# ATEM_Transmitter_v2.net
KiCad netlist of a schematic drawn in EAGLE
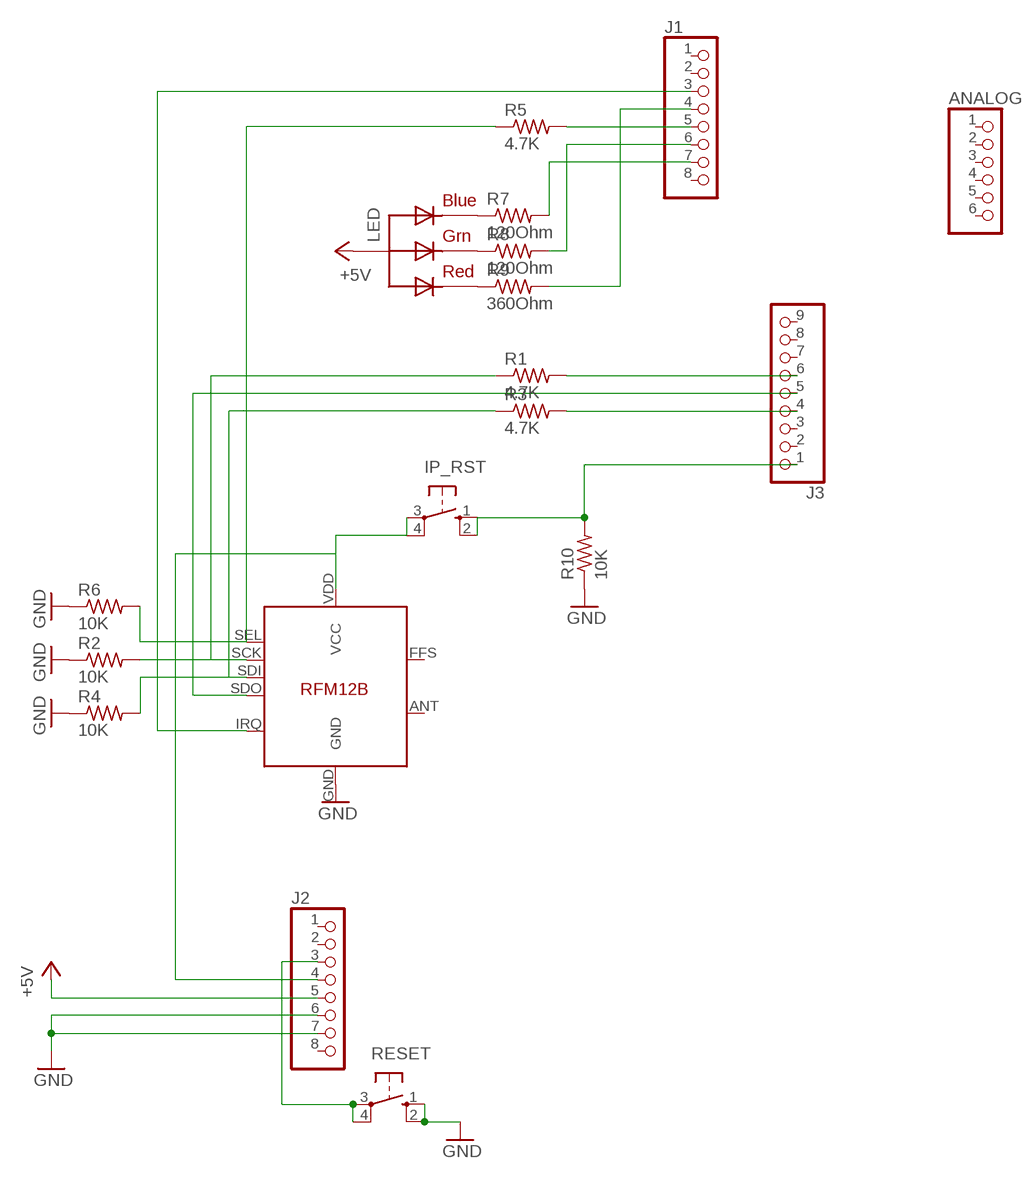
[diagram p0: schematic, sheet 1]

(export (version "E")
  (design (tool "Eeschema 10.0.6"))
  (components
    (comp (ref "ANALOG")
      (value "PINHD-1X6")
      (footprint "eagle-import:1X06")
      (libsource (lib "eagle-import") (part "PINHD-1X6"))
    )
    (comp (ref "IP_RST")
      (value "10-XX")
      (footprint "eagle-import:B3F-10XX")
      (libsource (lib "eagle-import") (part "10-XX"))
    )
    (comp (ref "J1")
      (value "PINHD-1X8TH")
      (footprint "eagle-import:1X08-TH")
      (libsource (lib "eagle-import") (part "PINHD-1X8TH"))
    )
    (comp (ref "J2")
      (value "PINHD-1X8TH")
      (footprint "eagle-import:1X08-TH")
      (libsource (lib "eagle-import") (part "PINHD-1X8TH"))
    )
    (comp (ref "J3")
      (value "PINHD-1X9")
      (footprint "eagle-import:1X09")
      (libsource (lib "eagle-import") (part "PINHD-1X9"))
    )
    (comp (ref "LED")
      (value "RGBLED_CA-5MM")
      (footprint "eagle-import:LED5MMRGB")
      (libsource (lib "eagle-import") (part "RGBLED_CA-5MM"))
    )
    (comp (ref "R1")
      (value "4.7K")
      (footprint "eagle-import:R0805")
      (libsource (lib "eagle-import") (part "R-US_R0805"))
    )
    (comp (ref "R2")
      (value "10K")
      (footprint "eagle-import:R0805")
      (libsource (lib "eagle-import") (part "R-US_R0805"))
    )
    (comp (ref "R3")
      (value "4.7K")
      (footprint "eagle-import:R0805")
      (libsource (lib "eagle-import") (part "R-US_R0805"))
    )
    (comp (ref "R4")
      (value "10K")
      (footprint "eagle-import:R0805")
      (libsource (lib "eagle-import") (part "R-US_R0805"))
    )
    (comp (ref "R5")
      (value "4.7K")
      (footprint "eagle-import:R0805")
      (libsource (lib "eagle-import") (part "R-US_R0805"))
    )
    (comp (ref "R6")
      (value "10K")
      (footprint "eagle-import:R0805")
      (libsource (lib "eagle-import") (part "R-US_R0805"))
    )
    (comp (ref "R7")
      (value "120Ohm")
      (footprint "eagle-import:R0805")
      (libsource (lib "eagle-import") (part "R-US_R0805"))
    )
    (comp (ref "R8")
      (value "120Ohm")
      (footprint "eagle-import:R0805")
      (libsource (lib "eagle-import") (part "R-US_R0805"))
    )
    (comp (ref "R9")
      (value "360Ohm")
      (footprint "eagle-import:R0805")
      (libsource (lib "eagle-import") (part "R-US_R0805"))
    )
    (comp (ref "R10")
      (value "10K")
      (footprint "eagle-import:R0805")
      (libsource (lib "eagle-import") (part "R-US_R0805"))
    )
    (comp (ref "RESET")
      (value "10-XX")
      (footprint "eagle-import:B3F-10XX")
      (libsource (lib "eagle-import") (part "10-XX"))
    )
    (comp (ref "U$2")
      (value "RFM12B")
      (footprint "eagle-import:LH-LIBRARY_RFM12B")
      (libsource (lib "eagle-import") (part "LH-LIBRARY_RFM12B"))
    )
  )
  (nets
    (net (code "1") (name "+5V") (class "Default")
      (node (ref "J2") (pin "5") (pinfunction "5_5") (pintype "passive"))
      (node (ref "LED") (pin "2") (pinfunction "VCC_2") (pintype "bidirectional"))
    )
    (net (code "2") (name "GND") (class "Default")
      (node (ref "J2") (pin "7") (pinfunction "7_7") (pintype "passive"))
      (node (ref "R10") (pin "1") (pinfunction "1_1") (pintype "passive"))
      (node (ref "R2") (pin "1") (pinfunction "1_1") (pintype "passive"))
      (node (ref "R4") (pin "1") (pinfunction "1_1") (pintype "passive"))
      (node (ref "R6") (pin "1") (pinfunction "1_1") (pintype "passive"))
      (node (ref "RESET") (pin "1") (pinfunction "S_1") (pintype "passive"))
      (node (ref "RESET") (pin "2") (pinfunction "S1_2") (pintype "passive"))
      (node (ref "U$2") (pin "GND") (pinfunction "GND_GND") (pintype "power_in"))
    )
    (net (code "3") (name "Net-(IP_RST-P)") (class "Default")
      (node (ref "IP_RST") (pin "3") (pinfunction "P_3") (pintype "passive"))
      (node (ref "IP_RST") (pin "4") (pinfunction "P1_4") (pintype "passive"))
      (node (ref "J2") (pin "4") (pinfunction "4_4") (pintype "passive"))
      (node (ref "U$2") (pin "VDD") (pinfunction "VCC_VDD") (pintype "power_in"))
    )
    (net (code "4") (name "Net-(IP_RST-S)") (class "Default")
      (node (ref "IP_RST") (pin "1") (pinfunction "S_1") (pintype "passive"))
      (node (ref "IP_RST") (pin "2") (pinfunction "S1_2") (pintype "passive"))
      (node (ref "J3") (pin "1") (pinfunction "1_1") (pintype "passive"))
      (node (ref "R10") (pin "2") (pinfunction "2_2") (pintype "passive"))
    )
    (net (code "5") (name "Net-(J1-Pad3)") (class "Default")
      (node (ref "J1") (pin "3") (pinfunction "3_3") (pintype "passive"))
      (node (ref "U$2") (pin "IRQ") (pinfunction "IRQ_IRQ") (pintype "open_collector"))
    )
    (net (code "6") (name "Net-(J1-Pad4)") (class "Default")
      (node (ref "J1") (pin "4") (pinfunction "4_4") (pintype "passive"))
      (node (ref "R9") (pin "2") (pinfunction "2_2") (pintype "passive"))
    )
    (net (code "7") (name "Net-(J1-Pad5)") (class "Default")
      (node (ref "J1") (pin "5") (pinfunction "5_5") (pintype "passive"))
      (node (ref "R5") (pin "2") (pinfunction "2_2") (pintype "passive"))
    )
    (net (code "8") (name "Net-(J1-Pad6)") (class "Default")
      (node (ref "J1") (pin "6") (pinfunction "6_6") (pintype "passive"))
      (node (ref "R8") (pin "2") (pinfunction "2_2") (pintype "passive"))
    )
    (net (code "9") (name "Net-(J1-Pad7)") (class "Default")
      (node (ref "J1") (pin "7") (pinfunction "7_7") (pintype "passive"))
      (node (ref "R7") (pin "2") (pinfunction "2_2") (pintype "passive"))
    )
    (net (code "10") (name "Net-(J3-Pad4)") (class "Default")
      (node (ref "J3") (pin "4") (pinfunction "4_4") (pintype "passive"))
      (node (ref "R3") (pin "2") (pinfunction "2_2") (pintype "passive"))
    )
    (net (code "11") (name "Net-(J3-Pad5)") (class "Default")
      (node (ref "J3") (pin "5") (pinfunction "5_5") (pintype "passive"))
      (node (ref "U$2") (pin "SDO") (pinfunction "SDO_SDO") (pintype "output"))
    )
    (net (code "12") (name "Net-(J3-Pad6)") (class "Default")
      (node (ref "J3") (pin "6") (pinfunction "6_6") (pintype "passive"))
      (node (ref "R1") (pin "2") (pinfunction "2_2") (pintype "passive"))
    )
    (net (code "13") (name "Net-(LED-BLUE)") (class "Default")
      (node (ref "LED") (pin "4") (pinfunction "BLUE_4") (pintype "bidirectional"))
      (node (ref "R7") (pin "1") (pinfunction "1_1") (pintype "passive"))
    )
    (net (code "14") (name "Net-(LED-GREEN)") (class "Default")
      (node (ref "LED") (pin "3") (pinfunction "GREEN_3") (pintype "bidirectional"))
      (node (ref "R8") (pin "1") (pinfunction "1_1") (pintype "passive"))
    )
    (net (code "15") (name "Net-(LED-RED)") (class "Default")
      (node (ref "LED") (pin "1") (pinfunction "RED_1") (pintype "bidirectional"))
      (node (ref "R9") (pin "1") (pinfunction "1_1") (pintype "passive"))
    )
    (net (code "16") (name "Net-(R1-Pad1)") (class "Default")
      (node (ref "R1") (pin "1") (pinfunction "1_1") (pintype "passive"))
      (node (ref "R2") (pin "2") (pinfunction "2_2") (pintype "passive"))
      (node (ref "U$2") (pin "SCK") (pinfunction "SCK_SCK") (pintype "input"))
    )
    (net (code "17") (name "Net-(R3-Pad1)") (class "Default")
      (node (ref "R3") (pin "1") (pinfunction "1_1") (pintype "passive"))
      (node (ref "R4") (pin "2") (pinfunction "2_2") (pintype "passive"))
      (node (ref "U$2") (pin "SDI") (pinfunction "SDI_SDI") (pintype "input"))
    )
    (net (code "18") (name "Net-(R5-Pad1)") (class "Default")
      (node (ref "R5") (pin "1") (pinfunction "1_1") (pintype "passive"))
      (node (ref "R6") (pin "2") (pinfunction "2_2") (pintype "passive"))
      (node (ref "U$2") (pin "SEL") (pinfunction "SEL_SEL") (pintype "input"))
    )
    (net (code "19") (name "Net-(RESET-P)") (class "Default")
      (node (ref "J2") (pin "3") (pinfunction "3_3") (pintype "passive"))
      (node (ref "RESET") (pin "3") (pinfunction "P_3") (pintype "passive"))
      (node (ref "RESET") (pin "4") (pinfunction "P1_4") (pintype "passive"))
    )
    (net (code "20") (name "unconnected-(ANALOG-Pad1)") (class "Default")
      (node (ref "ANALOG") (pin "1") (pinfunction "1_1") (pintype "passive"))
    )
    (net (code "21") (name "unconnected-(ANALOG-Pad2)") (class "Default")
      (node (ref "ANALOG") (pin "2") (pinfunction "2_2") (pintype "passive"))
    )
    (net (code "22") (name "unconnected-(ANALOG-Pad3)") (class "Default")
      (node (ref "ANALOG") (pin "3") (pinfunction "3_3") (pintype "passive"))
    )
    (net (code "23") (name "unconnected-(ANALOG-Pad4)") (class "Default")
      (node (ref "ANALOG") (pin "4") (pinfunction "4_4") (pintype "passive"))
    )
    (net (code "24") (name "unconnected-(ANALOG-Pad5)") (class "Default")
      (node (ref "ANALOG") (pin "5") (pinfunction "5_5") (pintype "passive"))
    )
    (net (code "25") (name "unconnected-(ANALOG-Pad6)") (class "Default")
      (node (ref "ANALOG") (pin "6") (pinfunction "6_6") (pintype "passive"))
    )
    (net (code "26") (name "unconnected-(J1-Pad1)") (class "Default")
      (node (ref "J1") (pin "1") (pinfunction "1_1") (pintype "passive"))
    )
    (net (code "27") (name "unconnected-(J1-Pad2)") (class "Default")
      (node (ref "J1") (pin "2") (pinfunction "2_2") (pintype "passive"))
    )
    (net (code "28") (name "unconnected-(J1-Pad8)") (class "Default")
      (node (ref "J1") (pin "8") (pinfunction "8_8") (pintype "passive"))
    )
    (net (code "29") (name "unconnected-(J2-Pad1)") (class "Default")
      (node (ref "J2") (pin "1") (pinfunction "1_1") (pintype "passive"))
    )
    (net (code "30") (name "unconnected-(J2-Pad2)") (class "Default")
      (node (ref "J2") (pin "2") (pinfunction "2_2") (pintype "passive"))
    )
    (net (code "31") (name "unconnected-(J2-Pad6)") (class "Default")
      (node (ref "J2") (pin "6") (pinfunction "6_6") (pintype "passive"))
    )
    (net (code "32") (name "unconnected-(J2-Pad8)") (class "Default")
      (node (ref "J2") (pin "8") (pinfunction "8_8") (pintype "passive"))
    )
    (net (code "33") (name "unconnected-(J3-Pad2)") (class "Default")
      (node (ref "J3") (pin "2") (pinfunction "2_2") (pintype "passive"))
    )
    (net (code "34") (name "unconnected-(J3-Pad3)") (class "Default")
      (node (ref "J3") (pin "3") (pinfunction "3_3") (pintype "passive"))
    )
    (net (code "35") (name "unconnected-(J3-Pad7)") (class "Default")
      (node (ref "J3") (pin "7") (pinfunction "7_7") (pintype "passive"))
    )
    (net (code "36") (name "unconnected-(J3-Pad8)") (class "Default")
      (node (ref "J3") (pin "8") (pinfunction "8_8") (pintype "passive"))
    )
    (net (code "37") (name "unconnected-(J3-Pad9)") (class "Default")
      (node (ref "J3") (pin "9") (pinfunction "9_9") (pintype "passive"))
    )
    (net (code "38") (name "unconnected-(U$2-PadANT)") (class "Default")
      (node (ref "U$2") (pin "ANT") (pinfunction "ANT_ANT") (pintype "passive"))
    )
    (net (code "39") (name "unconnected-(U$2-PadFFS)") (class "Default")
      (node (ref "U$2") (pin "FFS") (pinfunction "FFS_FFS") (pintype "bidirectional"))
    )
  )
)
